# MSSch.net
KiCad netlist of a schematic drawn in Altium Designer
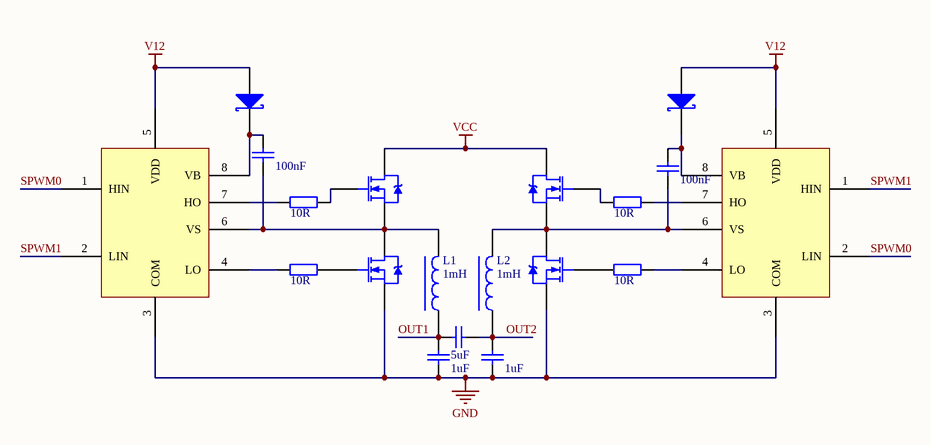
[diagram p0: MSSch.SchDoc]

(export (version "E")
  (design (tool "Eeschema 10.0.6"))
  (components
    (comp (ref "C1")
      (value "100nF")
      (footprint "0603C")
      (description "MLCC")
      (libsource (lib "Misc") (part "MLCC"))
    )
    (comp (ref "C2")
      (value "100nF")
      (footprint "0603C")
      (description "MLCC")
      (libsource (lib "Misc") (part "MLCC"))
    )
    (comp (ref "C3")
      (value "1uF")
      (footprint "0603C")
      (description "MLCC")
      (libsource (lib "Misc") (part "MLCC"))
    )
    (comp (ref "C4")
      (value "1uF")
      (footprint "0603C")
      (description "MLCC")
      (libsource (lib "Misc") (part "MLCC"))
    )
    (comp (ref "C5")
      (value "5uF")
      (footprint "0603C")
      (description "MLCC")
      (libsource (lib "Misc") (part "MLCC"))
    )
    (comp (ref "D1")
      (value "SS24")
      (footprint "SMA")
      (description "Schottky Rectifier")
      (libsource (lib "Misc") (part "SS24"))
    )
    (comp (ref "D2")
      (value "SS24")
      (footprint "SMA")
      (description "Schottky Rectifier")
      (libsource (lib "Misc") (part "SS24"))
    )
    (comp (ref "L1")
      (value "1mH")
      (footprint "CD32NP")
      (description "Power Inductor")
      (fields (field (name "Comment") "PowerInductor"))
      (libsource (lib "Misc") (part "PowerInductor"))
    )
    (comp (ref "L2")
      (value "1mH")
      (footprint "CD32NP")
      (description "Power Inductor")
      (fields (field (name "Comment") "PowerInductor"))
      (libsource (lib "Misc") (part "PowerInductor"))
    )
    (comp (ref "Q1")
      (value "NMOS")
      (footprint "DPAKUNI")
      (description "N-Channel Power MOSFET")
      (libsource (lib "Misc") (part "NMOS"))
    )
    (comp (ref "Q2")
      (value "NMOS")
      (footprint "DPAKUNI")
      (description "N-Channel Power MOSFET")
      (libsource (lib "Misc") (part "NMOS"))
    )
    (comp (ref "Q3")
      (value "NMOS")
      (footprint "DPAKUNI")
      (description "N-Channel Power MOSFET")
      (libsource (lib "Misc") (part "NMOS"))
    )
    (comp (ref "Q4")
      (value "NMOS")
      (footprint "DPAKUNI")
      (description "N-Channel Power MOSFET")
      (libsource (lib "Misc") (part "NMOS"))
    )
    (comp (ref "R1")
      (value "10R")
      (footprint "0402R")
      (description "Resistor")
      (libsource (lib "Misc") (part "Resistor"))
    )
    (comp (ref "R2")
      (value "10R")
      (footprint "0402R")
      (description "Resistor")
      (libsource (lib "Misc") (part "Resistor"))
    )
    (comp (ref "R3")
      (value "10R")
      (footprint "0402R")
      (description "Resistor")
      (libsource (lib "Misc") (part "Resistor"))
    )
    (comp (ref "R4")
      (value "10R")
      (footprint "0402R")
      (description "Resistor")
      (libsource (lib "Misc") (part "Resistor"))
    )
    (comp (ref "U1")
      (value "FAN7390")
      (footprint "SO-8_L")
      (description "High & Low side Gate Driver, 4.5A")
      (libsource (lib "FAN7390") (part "FAN7390"))
    )
    (comp (ref "U2")
      (value "FAN7390")
      (footprint "SO-8_L")
      (description "High & Low side Gate Driver, 4.5A")
      (libsource (lib "") (part "FAN7390_1"))
    )
  )
  (nets
    (net (code "1") (name "/OUT1") (class "Default")
      (node (ref "C3") (pin "2") (pinfunction "2_2") (pintype "passive"))
      (node (ref "C5") (pin "2") (pinfunction "2_2") (pintype "passive"))
      (node (ref "L1") (pin "1") (pinfunction "1_1") (pintype "passive"))
    )
    (net (code "2") (name "/OUT2") (class "Default")
      (node (ref "C4") (pin "2") (pinfunction "2_2") (pintype "passive"))
      (node (ref "C5") (pin "1") (pinfunction "1_1") (pintype "passive"))
      (node (ref "L2") (pin "1") (pinfunction "1_1") (pintype "passive"))
    )
    (net (code "3") (name "/SPWM0") (class "Default")
      (node (ref "U1") (pin "1") (pinfunction "HIN_1") (pintype "passive"))
      (node (ref "U2") (pin "2") (pinfunction "LIN_2") (pintype "passive"))
    )
    (net (code "4") (name "/SPWM1") (class "Default")
      (node (ref "U1") (pin "2") (pinfunction "LIN_2") (pintype "passive"))
      (node (ref "U2") (pin "1") (pinfunction "HIN_1") (pintype "passive"))
    )
    (net (code "5") (name "GND") (class "Default")
      (node (ref "C3") (pin "1") (pinfunction "1_1") (pintype "passive"))
      (node (ref "C4") (pin "1") (pinfunction "1_1") (pintype "passive"))
      (node (ref "Q2") (pin "3") (pinfunction "S_3") (pintype "passive"))
      (node (ref "Q4") (pin "3") (pinfunction "S_3") (pintype "passive"))
      (node (ref "U1") (pin "3") (pinfunction "COM_3") (pintype "passive"))
      (node (ref "U2") (pin "3") (pinfunction "COM_3") (pintype "passive"))
    )
    (net (code "6") (name "Net-(D1-K)") (class "Default")
      (node (ref "C1") (pin "2") (pinfunction "2_2") (pintype "passive"))
      (node (ref "D1") (pin "2") (pinfunction "K_2") (pintype "passive"))
      (node (ref "U1") (pin "8") (pinfunction "VB_8") (pintype "passive"))
    )
    (net (code "7") (name "Net-(D2-K)") (class "Default")
      (node (ref "C2") (pin "2") (pinfunction "2_2") (pintype "passive"))
      (node (ref "D2") (pin "2") (pinfunction "K_2") (pintype "passive"))
      (node (ref "U2") (pin "8") (pinfunction "VB_8") (pintype "passive"))
    )
    (net (code "8") (name "Net-(Q1-G)") (class "Default")
      (node (ref "Q1") (pin "1") (pinfunction "G_1") (pintype "passive"))
      (node (ref "R1") (pin "2") (pinfunction "2_2") (pintype "passive"))
    )
    (net (code "9") (name "Net-(Q1-S)") (class "Default")
      (node (ref "C1") (pin "1") (pinfunction "1_1") (pintype "passive"))
      (node (ref "L1") (pin "2") (pinfunction "2_2") (pintype "passive"))
      (node (ref "Q1") (pin "3") (pinfunction "S_3") (pintype "passive"))
      (node (ref "Q2") (pin "2") (pinfunction "D_2") (pintype "passive"))
      (node (ref "U1") (pin "6") (pinfunction "VS_6") (pintype "passive"))
    )
    (net (code "10") (name "Net-(Q2-G)") (class "Default")
      (node (ref "Q2") (pin "1") (pinfunction "G_1") (pintype "passive"))
      (node (ref "R2") (pin "2") (pinfunction "2_2") (pintype "passive"))
    )
    (net (code "11") (name "Net-(Q3-G)") (class "Default")
      (node (ref "Q3") (pin "1") (pinfunction "G_1") (pintype "passive"))
      (node (ref "R3") (pin "1") (pinfunction "1_1") (pintype "passive"))
    )
    (net (code "12") (name "Net-(Q3-S)") (class "Default")
      (node (ref "C2") (pin "1") (pinfunction "1_1") (pintype "passive"))
      (node (ref "L2") (pin "2") (pinfunction "2_2") (pintype "passive"))
      (node (ref "Q3") (pin "3") (pinfunction "S_3") (pintype "passive"))
      (node (ref "Q4") (pin "2") (pinfunction "D_2") (pintype "passive"))
      (node (ref "U2") (pin "6") (pinfunction "VS_6") (pintype "passive"))
    )
    (net (code "13") (name "Net-(Q4-G)") (class "Default")
      (node (ref "Q4") (pin "1") (pinfunction "G_1") (pintype "passive"))
      (node (ref "R4") (pin "1") (pinfunction "1_1") (pintype "passive"))
    )
    (net (code "14") (name "Net-(U1-HO)") (class "Default")
      (node (ref "R1") (pin "1") (pinfunction "1_1") (pintype "passive"))
      (node (ref "U1") (pin "7") (pinfunction "HO_7") (pintype "passive"))
    )
    (net (code "15") (name "Net-(U1-LO)") (class "Default")
      (node (ref "R2") (pin "1") (pinfunction "1_1") (pintype "passive"))
      (node (ref "U1") (pin "4") (pinfunction "LO_4") (pintype "passive"))
    )
    (net (code "16") (name "Net-(U2-HO)") (class "Default")
      (node (ref "R3") (pin "2") (pinfunction "2_2") (pintype "passive"))
      (node (ref "U2") (pin "7") (pinfunction "HO_7") (pintype "passive"))
    )
    (net (code "17") (name "Net-(U2-LO)") (class "Default")
      (node (ref "R4") (pin "2") (pinfunction "2_2") (pintype "passive"))
      (node (ref "U2") (pin "4") (pinfunction "LO_4") (pintype "passive"))
    )
    (net (code "18") (name "V12") (class "Default")
      (node (ref "D1") (pin "1") (pinfunction "A_1") (pintype "passive"))
      (node (ref "D2") (pin "1") (pinfunction "A_1") (pintype "passive"))
      (node (ref "U1") (pin "5") (pinfunction "VDD_5") (pintype "passive"))
      (node (ref "U2") (pin "5") (pinfunction "VDD_5") (pintype "passive"))
    )
    (net (code "19") (name "VCC") (class "Default")
      (node (ref "Q1") (pin "2") (pinfunction "D_2") (pintype "passive"))
      (node (ref "Q3") (pin "2") (pinfunction "D_2") (pintype "passive"))
    )
  )
)
